# gr10-1.net
KiCad netlist of a schematic drawn in EAGLE
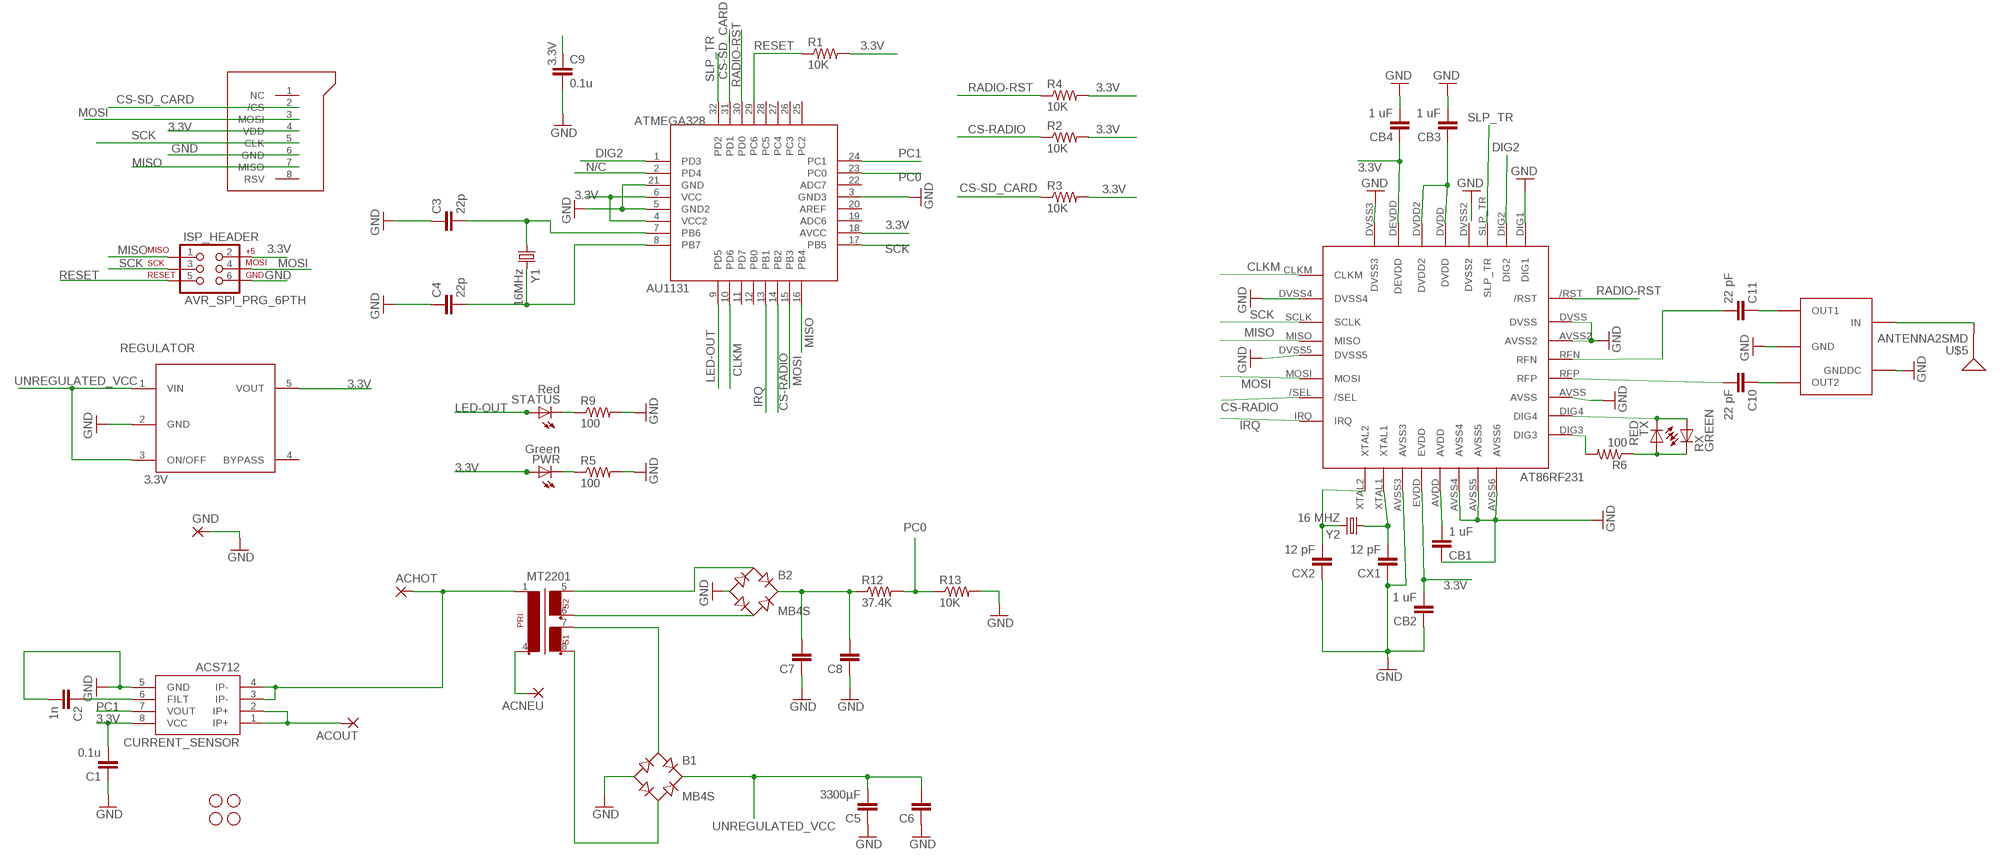
[diagram p0: schematic, sheet 1]

(export (version "E")
  (design (tool "Eeschema 10.0.6"))
  (components
    (comp (ref "3.3V_REGULATOR")
      (value "REG3.3V")
      (footprint "eagle-import:SOT23-5")
      (libsource (lib "eagle-import") (part "REG3.3V"))
    )
    (comp (ref "ACHOT")
      (value "3,81/1,4")
      (footprint "eagle-import:3,81_1,4")
      (libsource (lib "eagle-import") (part "3,81/1,4"))
    )
    (comp (ref "ACNEU")
      (value "3,81/1,4")
      (footprint "eagle-import:3,81_1,4")
      (libsource (lib "eagle-import") (part "3,81/1,4"))
    )
    (comp (ref "ACOUT")
      (value "3,81/1,4")
      (footprint "eagle-import:3,81_1,4")
      (libsource (lib "eagle-import") (part "3,81/1,4"))
    )
    (comp (ref "B1")
      (value "MB4S")
      (footprint "eagle-import:SOIC-4")
      (libsource (lib "eagle-import") (part "MBS4"))
    )
    (comp (ref "B2")
      (value "MB4S")
      (footprint "eagle-import:SOIC-4")
      (libsource (lib "eagle-import") (part "MBS4"))
    )
    (comp (ref "C1")
      (value "0.1u")
      (footprint "eagle-import:0603-CAP")
      (libsource (lib "eagle-import") (part "CAP0603-CAP"))
    )
    (comp (ref "C2")
      (value "1n")
      (footprint "eagle-import:0603-CAP")
      (libsource (lib "eagle-import") (part "CAP0603-CAP"))
    )
    (comp (ref "C3")
      (value "22p")
      (footprint "eagle-import:0603-CAP")
      (libsource (lib "eagle-import") (part "CAP0603-CAP"))
    )
    (comp (ref "C4")
      (value "22p")
      (footprint "eagle-import:0603-CAP")
      (libsource (lib "eagle-import") (part "CAP0603-CAP"))
    )
    (comp (ref "C5")
      (value "3300µF")
      (footprint "eagle-import:CAP-PTH-5MM")
      (libsource (lib "eagle-import") (part "CAPPTH1"))
    )
    (comp (ref "C6")
      (value "CAPPTH1")
      (footprint "eagle-import:CAP-PTH-5MM")
      (libsource (lib "eagle-import") (part "CAPPTH1"))
    )
    (comp (ref "C7")
      (value "CAPPTH1")
      (footprint "eagle-import:CAP-PTH-5MM")
      (libsource (lib "eagle-import") (part "CAPPTH1"))
    )
    (comp (ref "C8")
      (value "CAPPTH1")
      (footprint "eagle-import:CAP-PTH-5MM")
      (libsource (lib "eagle-import") (part "CAPPTH1"))
    )
    (comp (ref "C9")
      (value "0.1u")
      (footprint "eagle-import:0603-CAP")
      (libsource (lib "eagle-import") (part "CAP0603-CAP"))
    )
    (comp (ref "C10")
      (value "22 pF")
      (footprint "eagle-import:0603-CAP")
      (libsource (lib "eagle-import") (part "CAP0603-CAP"))
    )
    (comp (ref "C11")
      (value "22 pF")
      (footprint "eagle-import:0603-CAP")
      (libsource (lib "eagle-import") (part "CAP0603-CAP"))
    )
    (comp (ref "CB1")
      (value "1 uF")
      (footprint "eagle-import:0603-CAP")
      (libsource (lib "eagle-import") (part "CAP0603-CAP"))
    )
    (comp (ref "CB2")
      (value "1 uF")
      (footprint "eagle-import:0603-CAP")
      (libsource (lib "eagle-import") (part "CAP0603-CAP"))
    )
    (comp (ref "CB3")
      (value "1 uF")
      (footprint "eagle-import:0603-CAP")
      (libsource (lib "eagle-import") (part "CAP0603-CAP"))
    )
    (comp (ref "CB4")
      (value "1 uF")
      (footprint "eagle-import:0603-CAP")
      (libsource (lib "eagle-import") (part "CAP0603-CAP"))
    )
    (comp (ref "CURRENT_SENSOR")
      (value "ACS712")
      (footprint "eagle-import:SO08")
      (libsource (lib "eagle-import") (part "ACS712"))
    )
    (comp (ref "CX1")
      (value "12 pF")
      (footprint "eagle-import:0603-CAP")
      (libsource (lib "eagle-import") (part "CAP0603-CAP"))
    )
    (comp (ref "CX2")
      (value "12 pF")
      (footprint "eagle-import:0603-CAP")
      (libsource (lib "eagle-import") (part "CAP0603-CAP"))
    )
    (comp (ref "GND")
      (value "3,81/1,4")
      (footprint "eagle-import:3,81_1,4")
      (libsource (lib "eagle-import") (part "3,81/1,4"))
    )
    (comp (ref "ISP_HEADER")
      (value "AVR_SPI_PRG_6PTH")
      (footprint "eagle-import:2X3")
      (libsource (lib "eagle-import") (part "AVR_SPI_PRG_6PTH"))
    )
    (comp (ref "JP1")
      (value "STAND-OFF")
      (footprint "eagle-import:STAND-OFF")
      (libsource (lib "eagle-import") (part "STAND-OFF"))
    )
    (comp (ref "JP2")
      (value "STAND-OFF")
      (footprint "eagle-import:STAND-OFF")
      (libsource (lib "eagle-import") (part "STAND-OFF"))
    )
    (comp (ref "JP3")
      (value "STAND-OFF")
      (footprint "eagle-import:STAND-OFF")
      (libsource (lib "eagle-import") (part "STAND-OFF"))
    )
    (comp (ref "JP4")
      (value "STAND-OFF")
      (footprint "eagle-import:STAND-OFF")
      (libsource (lib "eagle-import") (part "STAND-OFF"))
    )
    (comp (ref "MT2201")
      (value "EI38-2")
      (footprint "eagle-import:EI38-2")
      (libsource (lib "eagle-import") (part "EI38-2"))
    )
    (comp (ref "PWR")
      (value "Green")
      (footprint "eagle-import:LED-0603")
      (libsource (lib "eagle-import") (part "LED0603"))
    )
    (comp (ref "R1")
      (value "10K")
      (footprint "eagle-import:0603-RES")
      (libsource (lib "eagle-import") (part "RESISTOR0603-RES"))
    )
    (comp (ref "R2")
      (value "10K")
      (footprint "eagle-import:0603-RES")
      (libsource (lib "eagle-import") (part "RESISTOR0603-RES"))
    )
    (comp (ref "R3")
      (value "10K")
      (footprint "eagle-import:0603-RES")
      (libsource (lib "eagle-import") (part "RESISTOR0603-RES"))
    )
    (comp (ref "R4")
      (value "10K")
      (footprint "eagle-import:0603-RES")
      (libsource (lib "eagle-import") (part "RESISTOR0603-RES"))
    )
    (comp (ref "R5")
      (value "100")
      (footprint "eagle-import:0603-RES")
      (libsource (lib "eagle-import") (part "RESISTOR0603-RES"))
    )
    (comp (ref "R6")
      (value "100")
      (footprint "eagle-import:0603-RES")
      (libsource (lib "eagle-import") (part "RESISTOR0603-RES"))
    )
    (comp (ref "R9")
      (value "100")
      (footprint "eagle-import:0603-RES")
      (libsource (lib "eagle-import") (part "RESISTOR0603-RES"))
    )
    (comp (ref "R12")
      (value "37.4K")
      (footprint "eagle-import:0603-RES")
      (libsource (lib "eagle-import") (part "RESISTOR0603-RES"))
    )
    (comp (ref "R13")
      (value "10K")
      (footprint "eagle-import:0603-RES")
      (libsource (lib "eagle-import") (part "RESISTOR0603-RES"))
    )
    (comp (ref "RX")
      (value "GREEN")
      (footprint "eagle-import:LED-0603")
      (libsource (lib "eagle-import") (part "LED0603"))
    )
    (comp (ref "STATUS")
      (value "Red")
      (footprint "eagle-import:LED-0603")
      (libsource (lib "eagle-import") (part "LED0603"))
    )
    (comp (ref "TX")
      (value "RED")
      (footprint "eagle-import:LED-0603")
      (libsource (lib "eagle-import") (part "LED0603"))
    )
    (comp (ref "U$1")
      (value "MICROSD")
      (footprint "eagle-import:MICRO-SD-SOCKET-PP")
      (libsource (lib "eagle-import") (part "MICROSD"))
    )
    (comp (ref "U$2")
      (value "ATMEGA32832A")
      (footprint "eagle-import:TQFP32-08")
      (libsource (lib "eagle-import") (part "ATMEGA32832A"))
    )
    (comp (ref "U$3")
      (value "AT86RF231(RADIO)AT86RF231")
      (footprint "eagle-import:32QN2(RADIO)")
      (libsource (lib "eagle-import") (part "AT86RF231(RADIO)AT86RF231"))
    )
    (comp (ref "U$4")
      (value "WE-BAL")
      (footprint "eagle-import:WE-BAL")
      (libsource (lib "eagle-import") (part "WE-BAL"))
    )
    (comp (ref "U$5")
      (value "ANTENNA2SMD")
      (footprint "eagle-import:ANTENNA-CHIP2")
      (libsource (lib "eagle-import") (part "ANTENNA2SMD"))
    )
    (comp (ref "Y1")
      (value "16MHz")
      (footprint "eagle-import:HC49UP")
      (libsource (lib "eagle-import") (part "CRYSTALSMD"))
    )
    (comp (ref "Y2")
      (value "16 MHZ")
      (footprint "eagle-import:HC49UP")
      (libsource (lib "eagle-import") (part "CRYSTALSMD"))
    )
  )
  (nets
    (net (code "1") (name "/3.3V") (class "Default")
      (node (ref "3.3V_REGULATOR") (pin "5") (pinfunction "VOUT_5") (pintype "bidirectional"))
      (node (ref "C1") (pin "2") (pinfunction "2_2") (pintype "passive"))
      (node (ref "C9") (pin "1") (pinfunction "1_1") (pintype "passive"))
      (node (ref "CB2") (pin "2") (pinfunction "2_2") (pintype "passive"))
      (node (ref "CB4") (pin "1") (pinfunction "1_1") (pintype "passive"))
      (node (ref "CURRENT_SENSOR") (pin "8") (pinfunction "VCC_8") (pintype "bidirectional"))
      (node (ref "ISP_HEADER") (pin "2") (pinfunction "2_2") (pintype "passive"))
      (node (ref "PWR") (pin "A") (pinfunction "A_A") (pintype "passive"))
      (node (ref "R1") (pin "2") (pinfunction "2_2") (pintype "passive"))
      (node (ref "R2") (pin "2") (pinfunction "2_2") (pintype "passive"))
      (node (ref "R3") (pin "2") (pinfunction "2_2") (pintype "passive"))
      (node (ref "R4") (pin "2") (pinfunction "2_2") (pintype "passive"))
      (node (ref "U$1") (pin "4") (pinfunction "VDD_4") (pintype "bidirectional"))
      (node (ref "U$2") (pin "18") (pinfunction "AVCC_18") (pintype "bidirectional"))
      (node (ref "U$2") (pin "4") (pinfunction "VCC2_4") (pintype "bidirectional"))
      (node (ref "U$2") (pin "6") (pinfunction "VCC_6") (pintype "bidirectional"))
      (node (ref "U$3") (pin "DEVDD") (pinfunction "DEVDD_DEVDD") (pintype "bidirectional"))
      (node (ref "U$3") (pin "EVDD") (pinfunction "EVDD_EVDD") (pintype "bidirectional"))
    )
    (net (code "2") (name "/CLKM") (class "Default")
      (node (ref "U$2") (pin "10") (pinfunction "PD6_10") (pintype "bidirectional"))
      (node (ref "U$3") (pin "CLKM") (pinfunction "CLKM_CLKM") (pintype "bidirectional"))
    )
    (net (code "3") (name "/CS-RADIO") (class "Default")
      (node (ref "R2") (pin "1") (pinfunction "1_1") (pintype "passive"))
      (node (ref "U$2") (pin "14") (pinfunction "PB2_14") (pintype "bidirectional"))
      (node (ref "U$3") (pin "/SEL") (pinfunction "/SEL_/SEL") (pintype "bidirectional"))
    )
    (net (code "4") (name "/CS-SD_CARD") (class "Default")
      (node (ref "R3") (pin "1") (pinfunction "1_1") (pintype "passive"))
      (node (ref "U$1") (pin "2") (pinfunction "/CS_2") (pintype "bidirectional"))
      (node (ref "U$2") (pin "31") (pinfunction "PD1_31") (pintype "bidirectional"))
    )
    (net (code "5") (name "/DIG2") (class "Default")
      (node (ref "U$2") (pin "1") (pinfunction "PD3_1") (pintype "bidirectional"))
      (node (ref "U$3") (pin "DIG2") (pinfunction "DIG2_DIG2") (pintype "bidirectional"))
    )
    (net (code "6") (name "/IRQ") (class "Default")
      (node (ref "U$2") (pin "13") (pinfunction "PB1_13") (pintype "bidirectional"))
      (node (ref "U$3") (pin "IRQ") (pinfunction "IRQ_IRQ") (pintype "bidirectional"))
    )
    (net (code "7") (name "/LED-OUT") (class "Default")
      (node (ref "STATUS") (pin "A") (pinfunction "A_A") (pintype "passive"))
      (node (ref "U$2") (pin "9") (pinfunction "PD5_9") (pintype "bidirectional"))
    )
    (net (code "8") (name "/MISO") (class "Default")
      (node (ref "ISP_HEADER") (pin "1") (pinfunction "1_1") (pintype "passive"))
      (node (ref "U$1") (pin "7") (pinfunction "MISO_7") (pintype "bidirectional"))
      (node (ref "U$2") (pin "16") (pinfunction "PB4_16") (pintype "bidirectional"))
      (node (ref "U$3") (pin "MISO") (pinfunction "MISO_MISO") (pintype "bidirectional"))
    )
    (net (code "9") (name "/MOSI") (class "Default")
      (node (ref "ISP_HEADER") (pin "4") (pinfunction "4_4") (pintype "passive"))
      (node (ref "U$1") (pin "3") (pinfunction "MOSI_3") (pintype "bidirectional"))
      (node (ref "U$2") (pin "15") (pinfunction "PB3_15") (pintype "bidirectional"))
      (node (ref "U$3") (pin "MOSI") (pinfunction "MOSI_MOSI") (pintype "bidirectional"))
    )
    (net (code "10") (name "/N{slash}C") (class "Default")
      (node (ref "U$2") (pin "2") (pinfunction "PD4_2") (pintype "bidirectional"))
    )
    (net (code "11") (name "/PC0") (class "Default")
      (node (ref "R12") (pin "2") (pinfunction "2_2") (pintype "passive"))
      (node (ref "R13") (pin "1") (pinfunction "1_1") (pintype "passive"))
      (node (ref "U$2") (pin "23") (pinfunction "PC0_23") (pintype "bidirectional"))
    )
    (net (code "12") (name "/PC1") (class "Default")
      (node (ref "CURRENT_SENSOR") (pin "7") (pinfunction "VOUT_7") (pintype "bidirectional"))
      (node (ref "U$2") (pin "24") (pinfunction "PC1_24") (pintype "bidirectional"))
    )
    (net (code "13") (name "/RADIO-RST") (class "Default")
      (node (ref "R4") (pin "1") (pinfunction "1_1") (pintype "passive"))
      (node (ref "U$2") (pin "30") (pinfunction "PD0_30") (pintype "bidirectional"))
      (node (ref "U$3") (pin "/RST") (pinfunction "/RST_/RST") (pintype "bidirectional"))
    )
    (net (code "14") (name "/RESET") (class "Default")
      (node (ref "ISP_HEADER") (pin "5") (pinfunction "5_5") (pintype "passive"))
      (node (ref "R1") (pin "1") (pinfunction "1_1") (pintype "passive"))
      (node (ref "U$2") (pin "29") (pinfunction "PC6_29") (pintype "bidirectional"))
    )
    (net (code "15") (name "/SCK") (class "Default")
      (node (ref "ISP_HEADER") (pin "3") (pinfunction "3_3") (pintype "passive"))
      (node (ref "U$1") (pin "5") (pinfunction "CLK_5") (pintype "bidirectional"))
      (node (ref "U$2") (pin "17") (pinfunction "PB5_17") (pintype "bidirectional"))
      (node (ref "U$3") (pin "SCLK") (pinfunction "SCLK_SCLK") (pintype "bidirectional"))
    )
    (net (code "16") (name "/SLP_TR") (class "Default")
      (node (ref "U$2") (pin "32") (pinfunction "PD2_32") (pintype "bidirectional"))
      (node (ref "U$3") (pin "SLP_TR") (pinfunction "SLP_TR_SLP_TR") (pintype "bidirectional"))
    )
    (net (code "17") (name "/UNREGULATED_VCC") (class "Default")
      (node (ref "3.3V_REGULATOR") (pin "1") (pinfunction "VIN_1") (pintype "bidirectional"))
      (node (ref "3.3V_REGULATOR") (pin "3") (pinfunction "ON/OFF_3") (pintype "bidirectional"))
      (node (ref "B1") (pin "+") (pinfunction "+_+") (pintype "passive"))
      (node (ref "C5") (pin "2") (pinfunction "2_2") (pintype "passive"))
      (node (ref "C6") (pin "2") (pinfunction "2_2") (pintype "passive"))
    )
    (net (code "18") (name "GND") (class "Default")
      (node (ref "3.3V_REGULATOR") (pin "2") (pinfunction "GND_2") (pintype "bidirectional"))
      (node (ref "B1") (pin "-") (pinfunction "-_-") (pintype "passive"))
      (node (ref "B2") (pin "-") (pinfunction "-_-") (pintype "passive"))
      (node (ref "C1") (pin "1") (pinfunction "1_1") (pintype "passive"))
      (node (ref "C2") (pin "2") (pinfunction "2_2") (pintype "passive"))
      (node (ref "C3") (pin "1") (pinfunction "1_1") (pintype "passive"))
      (node (ref "C4") (pin "1") (pinfunction "1_1") (pintype "passive"))
      (node (ref "C5") (pin "1") (pinfunction "1_1") (pintype "passive"))
      (node (ref "C6") (pin "1") (pinfunction "1_1") (pintype "passive"))
      (node (ref "C7") (pin "1") (pinfunction "1_1") (pintype "passive"))
      (node (ref "C8") (pin "1") (pinfunction "1_1") (pintype "passive"))
      (node (ref "C9") (pin "2") (pinfunction "2_2") (pintype "passive"))
      (node (ref "CB1") (pin "1") (pinfunction "1_1") (pintype "passive"))
      (node (ref "CB2") (pin "1") (pinfunction "1_1") (pintype "passive"))
      (node (ref "CB3") (pin "2") (pinfunction "2_2") (pintype "passive"))
      (node (ref "CB4") (pin "2") (pinfunction "2_2") (pintype "passive"))
      (node (ref "CURRENT_SENSOR") (pin "5") (pinfunction "GND_5") (pintype "bidirectional"))
      (node (ref "CX1") (pin "1") (pinfunction "1_1") (pintype "passive"))
      (node (ref "CX2") (pin "1") (pinfunction "1_1") (pintype "passive"))
      (node (ref "GND") (pin "1") (pinfunction "P_1") (pintype "passive"))
      (node (ref "ISP_HEADER") (pin "6") (pinfunction "6_6") (pintype "passive"))
      (node (ref "R13") (pin "2") (pinfunction "2_2") (pintype "passive"))
      (node (ref "R5") (pin "2") (pinfunction "2_2") (pintype "passive"))
      (node (ref "R9") (pin "2") (pinfunction "2_2") (pintype "passive"))
      (node (ref "U$1") (pin "6") (pinfunction "GND_6") (pintype "bidirectional"))
      (node (ref "U$2") (pin "21") (pinfunction "GND_21") (pintype "bidirectional"))
      (node (ref "U$2") (pin "3") (pinfunction "GND3_3") (pintype "bidirectional"))
      (node (ref "U$2") (pin "5") (pinfunction "GND2_5") (pintype "bidirectional"))
      (node (ref "U$3") (pin "AVSS") (pinfunction "AVSS_AVSS") (pintype "bidirectional"))
      (node (ref "U$3") (pin "AVSS2") (pinfunction "AVSS2_AVSS2") (pintype "bidirectional"))
      (node (ref "U$3") (pin "AVSS3") (pinfunction "AVSS3_AVSS3") (pintype "bidirectional"))
      (node (ref "U$3") (pin "AVSS4") (pinfunction "AVSS4_AVSS4") (pintype "bidirectional"))
      (node (ref "U$3") (pin "AVSS5") (pinfunction "AVSS5_AVSS5") (pintype "bidirectional"))
      (node (ref "U$3") (pin "AVSS6") (pinfunction "AVSS6_AVSS6") (pintype "bidirectional"))
      (node (ref "U$3") (pin "DIG1") (pinfunction "DIG1_DIG1") (pintype "bidirectional"))
      (node (ref "U$3") (pin "DVSS") (pinfunction "DVSS_DVSS") (pintype "bidirectional"))
      (node (ref "U$3") (pin "DVSS3") (pinfunction "DVSS3_DVSS3") (pintype "bidirectional"))
      (node (ref "U$3") (pin "DVSS4") (pinfunction "DVSS4_DVSS4") (pintype "bidirectional"))
      (node (ref "U$3") (pin "DVSS5") (pinfunction "DVSS5_DVSS5") (pintype "bidirectional"))
      (node (ref "U$4") (pin "GND") (pinfunction "GND_GND") (pintype "bidirectional"))
      (node (ref "U$4") (pin "GNDDC") (pinfunction "GNDDC_GNDDC") (pintype "bidirectional"))
    )
    (net (code "19") (name "Net-(ACHOT-P)") (class "Default")
      (node (ref "ACHOT") (pin "1") (pinfunction "P_1") (pintype "passive"))
      (node (ref "CURRENT_SENSOR") (pin "3") (pinfunction "IP-_3") (pintype "bidirectional"))
      (node (ref "CURRENT_SENSOR") (pin "4") (pinfunction "IP-_4") (pintype "bidirectional"))
      (node (ref "MT2201") (pin "1") (pinfunction "1_1") (pintype "passive"))
    )
    (net (code "20") (name "Net-(ACNEU-P)") (class "Default")
      (node (ref "ACNEU") (pin "1") (pinfunction "P_1") (pintype "passive"))
      (node (ref "MT2201") (pin "4") (pinfunction "4_4") (pintype "passive"))
    )
    (net (code "21") (name "Net-(ACOUT-P)") (class "Default")
      (node (ref "ACOUT") (pin "1") (pinfunction "P_1") (pintype "passive"))
      (node (ref "CURRENT_SENSOR") (pin "1") (pinfunction "IP+_1") (pintype "bidirectional"))
      (node (ref "CURRENT_SENSOR") (pin "2") (pinfunction "IP+_2") (pintype "bidirectional"))
    )
    (net (code "22") (name "Net-(B1-AC1)") (class "Default")
      (node (ref "B1") (pin "~1") (pinfunction "AC1_~1") (pintype "passive"))
      (node (ref "MT2201") (pin "7") (pinfunction "7_7") (pintype "passive"))
    )
    (net (code "23") (name "Net-(B1-AC2)") (class "Default")
      (node (ref "B1") (pin "~2") (pinfunction "AC2_~2") (pintype "passive"))
      (node (ref "MT2201") (pin "8") (pinfunction "8_8") (pintype "passive"))
    )
    (net (code "24") (name "Net-(B2-AC1)") (class "Default")
      (node (ref "B2") (pin "~1") (pinfunction "AC1_~1") (pintype "passive"))
      (node (ref "MT2201") (pin "5") (pinfunction "5_5") (pintype "passive"))
    )
    (net (code "25") (name "Net-(B2-AC2)") (class "Default")
      (node (ref "B2") (pin "~2") (pinfunction "AC2_~2") (pintype "passive"))
      (node (ref "MT2201") (pin "6") (pinfunction "6_6") (pintype "passive"))
    )
    (net (code "26") (name "Net-(B2-Pad+)") (class "Default")
      (node (ref "B2") (pin "+") (pinfunction "+_+") (pintype "passive"))
      (node (ref "C7") (pin "2") (pinfunction "2_2") (pintype "passive"))
      (node (ref "C8") (pin "2") (pinfunction "2_2") (pintype "passive"))
      (node (ref "R12") (pin "1") (pinfunction "1_1") (pintype "passive"))
    )
    (net (code "27") (name "Net-(C10-Pad1)") (class "Default")
      (node (ref "C10") (pin "1") (pinfunction "1_1") (pintype "passive"))
      (node (ref "U$4") (pin "OUT2") (pinfunction "OUT2_OUT2") (pintype "bidirectional"))
    )
    (net (code "28") (name "Net-(C10-Pad2)") (class "Default")
      (node (ref "C10") (pin "2") (pinfunction "2_2") (pintype "passive"))
      (node (ref "U$3") (pin "RFP") (pinfunction "RFP_RFP") (pintype "bidirectional"))
    )
    (net (code "29") (name "Net-(C11-Pad1)") (class "Default")
      (node (ref "C11") (pin "1") (pinfunction "1_1") (pintype "passive"))
      (node (ref "U$4") (pin "OUT1") (pinfunction "OUT1_OUT1") (pintype "bidirectional"))
    )
    (net (code "30") (name "Net-(C11-Pad2)") (class "Default")
      (node (ref "C11") (pin "2") (pinfunction "2_2") (pintype "passive"))
      (node (ref "U$3") (pin "RFN") (pinfunction "RFN_RFN") (pintype "bidirectional"))
    )
    (net (code "31") (name "Net-(CB1-Pad2)") (class "Default")
      (node (ref "CB1") (pin "2") (pinfunction "2_2") (pintype "passive"))
      (node (ref "U$3") (pin "AVDD") (pinfunction "AVDD_AVDD") (pintype "bidirectional"))
    )
    (net (code "32") (name "Net-(CB3-Pad1)") (class "Default")
      (node (ref "CB3") (pin "1") (pinfunction "1_1") (pintype "passive"))
      (node (ref "U$3") (pin "DVDD") (pinfunction "DVDD_DVDD") (pintype "bidirectional"))
      (node (ref "U$3") (pin "DVDD2") (pinfunction "DVDD2_DVDD2") (pintype "bidirectional"))
    )
    (net (code "33") (name "Net-(CURRENT_SENSOR-FILT)") (class "Default")
      (node (ref "C2") (pin "1") (pinfunction "1_1") (pintype "passive"))
      (node (ref "CURRENT_SENSOR") (pin "6") (pinfunction "FILT_6") (pintype "bidirectional"))
    )
    (net (code "34") (name "Net-(CX1-Pad2)") (class "Default")
      (node (ref "CX1") (pin "2") (pinfunction "2_2") (pintype "passive"))
      (node (ref "U$3") (pin "XTAL1") (pinfunction "XTAL1_XTAL1") (pintype "bidirectional"))
      (node (ref "Y2") (pin "1") (pinfunction "1_1") (pintype "passive"))
    )
    (net (code "35") (name "Net-(CX2-Pad2)") (class "Default")
      (node (ref "CX2") (pin "2") (pinfunction "2_2") (pintype "passive"))
      (node (ref "U$3") (pin "XTAL2") (pinfunction "XTAL2_XTAL2") (pintype "bidirectional"))
      (node (ref "Y2") (pin "2") (pinfunction "2_2") (pintype "passive"))
    )
    (net (code "36") (name "Net-(PWR-PadC)") (class "Default")
      (node (ref "PWR") (pin "C") (pinfunction "C_C") (pintype "passive"))
      (node (ref "R5") (pin "1") (pinfunction "1_1") (pintype "passive"))
    )
    (net (code "37") (name "Net-(R6-Pad1)") (class "Default")
      (node (ref "R6") (pin "1") (pinfunction "1_1") (pintype "passive"))
      (node (ref "RX") (pin "C") (pinfunction "C_C") (pintype "passive"))
      (node (ref "TX") (pin "A") (pinfunction "A_A") (pintype "passive"))
    )
    (net (code "38") (name "Net-(R6-Pad2)") (class "Default")
      (node (ref "R6") (pin "2") (pinfunction "2_2") (pintype "passive"))
      (node (ref "U$3") (pin "DIG3") (pinfunction "DIG3_DIG3") (pintype "bidirectional"))
    )
    (net (code "39") (name "Net-(R9-Pad1)") (class "Default")
      (node (ref "R9") (pin "1") (pinfunction "1_1") (pintype "passive"))
      (node (ref "STATUS") (pin "C") (pinfunction "C_C") (pintype "passive"))
    )
    (net (code "40") (name "Net-(RX-PadA)") (class "Default")
      (node (ref "RX") (pin "A") (pinfunction "A_A") (pintype "passive"))
      (node (ref "TX") (pin "C") (pinfunction "C_C") (pintype "passive"))
      (node (ref "U$3") (pin "DIG4") (pinfunction "DIG4_DIG4") (pintype "bidirectional"))
    )
    (net (code "41") (name "Net-(U$2-PB6)") (class "Default")
      (node (ref "C3") (pin "2") (pinfunction "2_2") (pintype "passive"))
      (node (ref "U$2") (pin "7") (pinfunction "PB6_7") (pintype "bidirectional"))
      (node (ref "Y1") (pin "1") (pinfunction "1_1") (pintype "passive"))
    )
    (net (code "42") (name "Net-(U$2-PB7)") (class "Default")
      (node (ref "C4") (pin "2") (pinfunction "2_2") (pintype "passive"))
      (node (ref "U$2") (pin "8") (pinfunction "PB7_8") (pintype "bidirectional"))
      (node (ref "Y1") (pin "2") (pinfunction "2_2") (pintype "passive"))
    )
    (net (code "43") (name "Net-(U$5-SIGNAL)") (class "Default")
      (node (ref "U$4") (pin "IN") (pinfunction "IN_IN") (pintype "bidirectional"))
      (node (ref "U$5") (pin "FEED") (pinfunction "SIGNAL_FEED") (pintype "bidirectional"))
    )
    (net (code "44") (name "unconnected-(3.3V_REGULATOR-BYPASS-Pad4)") (class "Default")
      (node (ref "3.3V_REGULATOR") (pin "4") (pinfunction "BYPASS_4") (pintype "bidirectional"))
    )
    (net (code "45") (name "unconnected-(U$1-NC-Pad1)") (class "Default")
      (node (ref "U$1") (pin "1") (pinfunction "NC_1") (pintype "bidirectional"))
    )
    (net (code "46") (name "unconnected-(U$1-RSV-Pad8)") (class "Default")
      (node (ref "U$1") (pin "8") (pinfunction "RSV_8") (pintype "bidirectional"))
    )
    (net (code "47") (name "unconnected-(U$2-ADC6-Pad19)") (class "Default")
      (node (ref "U$2") (pin "19") (pinfunction "ADC6_19") (pintype "bidirectional"))
    )
    (net (code "48") (name "unconnected-(U$2-ADC7-Pad22)") (class "Default")
      (node (ref "U$2") (pin "22") (pinfunction "ADC7_22") (pintype "bidirectional"))
    )
    (net (code "49") (name "unconnected-(U$2-AREF-Pad20)") (class "Default")
      (node (ref "U$2") (pin "20") (pinfunction "AREF_20") (pintype "bidirectional"))
    )
    (net (code "50") (name "unconnected-(U$2-PB0-Pad12)") (class "Default")
      (node (ref "U$2") (pin "12") (pinfunction "PB0_12") (pintype "bidirectional"))
    )
    (net (code "51") (name "unconnected-(U$2-PC2-Pad25)") (class "Default")
      (node (ref "U$2") (pin "25") (pinfunction "PC2_25") (pintype "bidirectional"))
    )
    (net (code "52") (name "unconnected-(U$2-PC3-Pad26)") (class "Default")
      (node (ref "U$2") (pin "26") (pinfunction "PC3_26") (pintype "bidirectional"))
    )
    (net (code "53") (name "unconnected-(U$2-PC4-Pad27)") (class "Default")
      (node (ref "U$2") (pin "27") (pinfunction "PC4_27") (pintype "bidirectional"))
    )
    (net (code "54") (name "unconnected-(U$2-PC5-Pad28)") (class "Default")
      (node (ref "U$2") (pin "28") (pinfunction "PC5_28") (pintype "bidirectional"))
    )
    (net (code "55") (name "unconnected-(U$2-PD7-Pad11)") (class "Default")
      (node (ref "U$2") (pin "11") (pinfunction "PD7_11") (pintype "bidirectional"))
    )
    (net (code "56") (name "unconnected-(U$3-PadDVSS2)") (class "Default")
      (node (ref "U$3") (pin "DVSS2") (pinfunction "DVSS2_DVSS2") (pintype "bidirectional"))
    )
  )
)
